# MeshSync.net
KiCad netlist of a schematic drawn in EAGLE
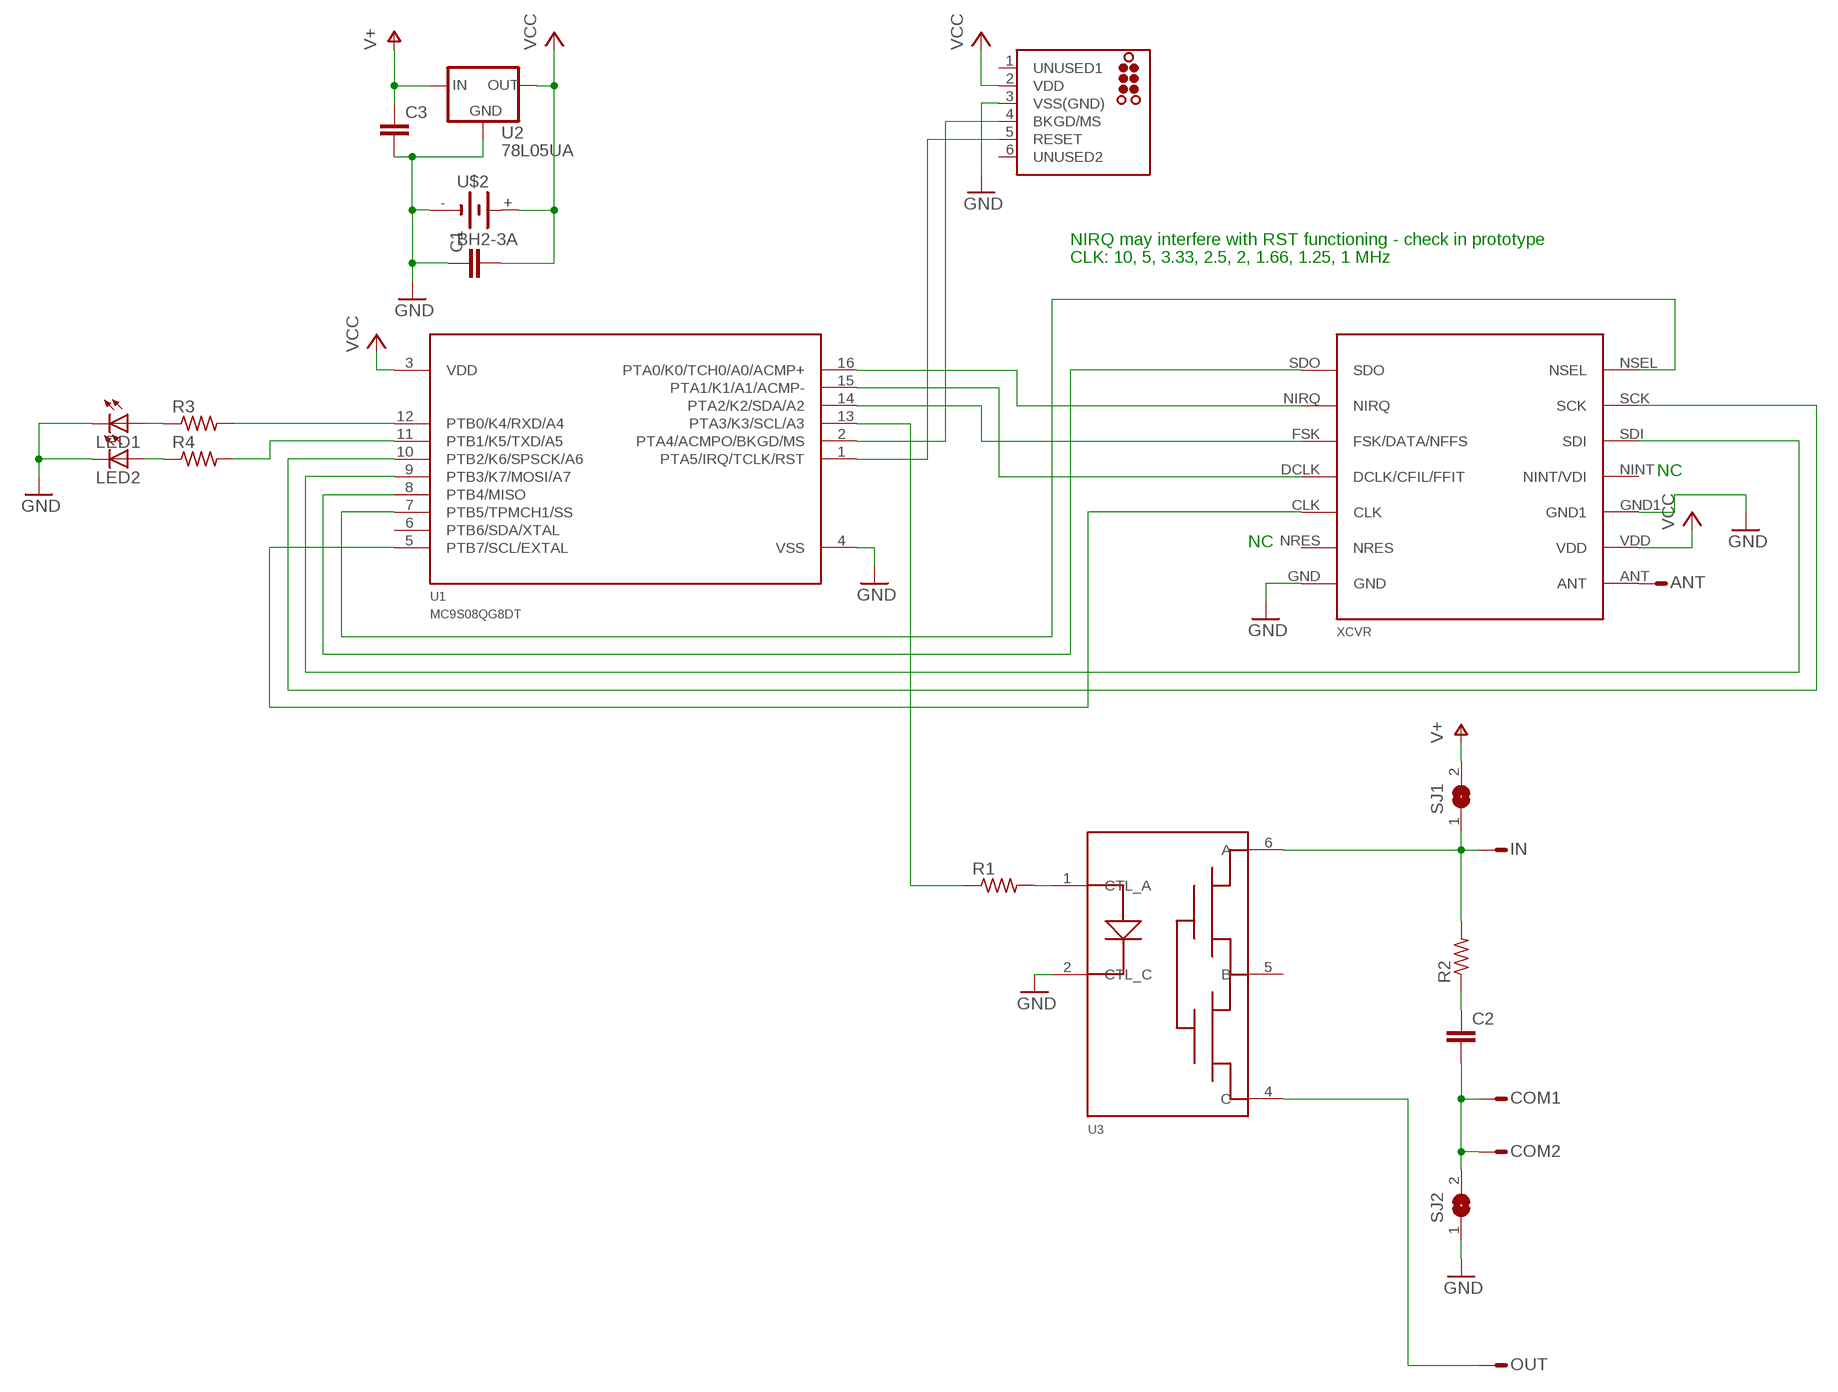
[diagram p0: schematic, sheet 1]

(export (version "E")
  (design (tool "Eeschema 10.0.6"))
  (components
    (comp (ref "ANT")
      (value "PIN")
      (footprint "eagle-import:PINHEAD-1")
      (libsource (lib "eagle-import") (part "PIN"))
    )
    (comp (ref "C1")
      (value "C-EUC0805K")
      (footprint "eagle-import:C0805K")
      (libsource (lib "eagle-import") (part "C-EUC0805K"))
    )
    (comp (ref "C2")
      (value "C-EUC0603K")
      (footprint "eagle-import:C0603K")
      (libsource (lib "eagle-import") (part "C-EUC0603K"))
    )
    (comp (ref "C3")
      (value "C-EUC0603K")
      (footprint "eagle-import:C0603K")
      (libsource (lib "eagle-import") (part "C-EUC0603K"))
    )
    (comp (ref "COM1")
      (value "PIN")
      (footprint "eagle-import:PINHEAD-1")
      (libsource (lib "eagle-import") (part "PIN"))
    )
    (comp (ref "COM2")
      (value "PIN")
      (footprint "eagle-import:PINHEAD-1")
      (libsource (lib "eagle-import") (part "PIN"))
    )
    (comp (ref "IN")
      (value "PIN")
      (footprint "eagle-import:PINHEAD-1")
      (libsource (lib "eagle-import") (part "PIN"))
    )
    (comp (ref "LED1")
      (value "LEDCHIPLED_0603")
      (footprint "eagle-import:CHIPLED_0603")
      (libsource (lib "eagle-import") (part "LEDCHIPLED_0603"))
    )
    (comp (ref "LED2")
      (value "LEDCHIPLED_0603")
      (footprint "eagle-import:CHIPLED_0603")
      (libsource (lib "eagle-import") (part "LEDCHIPLED_0603"))
    )
    (comp (ref "OUT")
      (value "PIN")
      (footprint "eagle-import:PINHEAD-1")
      (libsource (lib "eagle-import") (part "PIN"))
    )
    (comp (ref "R1")
      (value "R0603")
      (footprint "eagle-import:R0603")
      (libsource (lib "eagle-import") (part "R0603"))
    )
    (comp (ref "R2")
      (value "R0603")
      (footprint "eagle-import:R0603")
      (libsource (lib "eagle-import") (part "R0603"))
    )
    (comp (ref "R3")
      (value "R0603")
      (footprint "eagle-import:R0603")
      (libsource (lib "eagle-import") (part "R0603"))
    )
    (comp (ref "R4")
      (value "R0603")
      (footprint "eagle-import:R0603")
      (libsource (lib "eagle-import") (part "R0603"))
    )
    (comp (ref "SJ1")
      (value "SJW")
      (footprint "eagle-import:SJW")
      (libsource (lib "eagle-import") (part "SJW"))
    )
    (comp (ref "SJ2")
      (value "SJW")
      (footprint "eagle-import:SJW")
      (libsource (lib "eagle-import") (part "SJW"))
    )
    (comp (ref "U$1")
      (value "TC2030-MCP-NL")
      (footprint "eagle-import:TC2030-MCP-NL")
      (libsource (lib "eagle-import") (part "TC2030-MCP-NL"))
    )
    (comp (ref "U$2")
      (value "BH2-3A")
      (footprint "eagle-import:BH2-3A")
      (libsource (lib "eagle-import") (part "BH2-3A"))
    )
    (comp (ref "U1")
      (value "MC9S08QG8DT")
      (footprint "eagle-import:TSSOP16")
      (libsource (lib "eagle-import") (part "MC9S08QG8DT"))
    )
    (comp (ref "U2")
      (value "78L05UA")
      (footprint "eagle-import:SOT89")
      (libsource (lib "eagle-import") (part "78L05UA"))
    )
    (comp (ref "U3")
      (value "PVT312")
      (footprint "eagle-import:DIL06-SMT")
      (libsource (lib "eagle-import") (part "PVT312"))
    )
    (comp (ref "XCVR")
      (value "RFM12B")
      (footprint "eagle-import:RFM12B")
      (libsource (lib "eagle-import") (part "RFM12B"))
    )
  )
  (nets
    (net (code "1") (name "GND") (class "Default")
      (node (ref "C1") (pin "1") (pinfunction "1_1") (pintype "passive"))
      (node (ref "C3") (pin "2") (pinfunction "2_2") (pintype "passive"))
      (node (ref "LED1") (pin "C") (pinfunction "C_C") (pintype "passive"))
      (node (ref "LED2") (pin "C") (pinfunction "C_C") (pintype "passive"))
      (node (ref "SJ2") (pin "1") (pinfunction "1_1") (pintype "passive"))
      (node (ref "U$1") (pin "3") (pinfunction "VSS(GND)_3") (pintype "power_in"))
      (node (ref "U$2") (pin "-") (pinfunction "-_-") (pintype "passive"))
      (node (ref "U1") (pin "4") (pinfunction "VSS_4") (pintype "bidirectional"))
      (node (ref "U2") (pin "2") (pinfunction "GND_2") (pintype "input"))
      (node (ref "U3") (pin "2") (pinfunction "CTL_C_2") (pintype "bidirectional"))
      (node (ref "XCVR") (pin "GND") (pinfunction "GND_GND") (pintype "bidirectional"))
      (node (ref "XCVR") (pin "GND1") (pinfunction "GND1_GND1") (pintype "bidirectional"))
    )
    (net (code "2") (name "Net-(ANT-M)") (class "Default")
      (node (ref "ANT") (pin "1") (pinfunction "M_1") (pintype "passive"))
      (node (ref "XCVR") (pin "ANT") (pinfunction "ANT_ANT") (pintype "bidirectional"))
    )
    (net (code "3") (name "Net-(C2-Pad1)") (class "Default")
      (node (ref "C2") (pin "1") (pinfunction "1_1") (pintype "passive"))
      (node (ref "R2") (pin "1") (pinfunction "1_1") (pintype "passive"))
    )
    (net (code "4") (name "Net-(COM1-M)") (class "Default")
      (node (ref "C2") (pin "2") (pinfunction "2_2") (pintype "passive"))
      (node (ref "COM1") (pin "1") (pinfunction "M_1") (pintype "passive"))
      (node (ref "COM2") (pin "1") (pinfunction "M_1") (pintype "passive"))
      (node (ref "SJ2") (pin "2") (pinfunction "2_2") (pintype "passive"))
    )
    (net (code "5") (name "Net-(IN-M)") (class "Default")
      (node (ref "IN") (pin "1") (pinfunction "M_1") (pintype "passive"))
      (node (ref "R2") (pin "2") (pinfunction "2_2") (pintype "passive"))
      (node (ref "SJ1") (pin "1") (pinfunction "1_1") (pintype "passive"))
      (node (ref "U3") (pin "6") (pinfunction "A_6") (pintype "bidirectional"))
    )
    (net (code "6") (name "Net-(LED1-PadA)") (class "Default")
      (node (ref "LED1") (pin "A") (pinfunction "A_A") (pintype "passive"))
      (node (ref "R3") (pin "1") (pinfunction "1_1") (pintype "passive"))
    )
    (net (code "7") (name "Net-(LED2-PadA)") (class "Default")
      (node (ref "LED2") (pin "A") (pinfunction "A_A") (pintype "passive"))
      (node (ref "R4") (pin "1") (pinfunction "1_1") (pintype "passive"))
    )
    (net (code "8") (name "Net-(OUT-M)") (class "Default")
      (node (ref "OUT") (pin "1") (pinfunction "M_1") (pintype "passive"))
      (node (ref "U3") (pin "4") (pinfunction "C_4") (pintype "bidirectional"))
    )
    (net (code "9") (name "Net-(U$1-BKGD{slash}MS)") (class "Default")
      (node (ref "U$1") (pin "4") (pinfunction "BKGD/MS_4") (pintype "bidirectional"))
      (node (ref "U1") (pin "2") (pinfunction "PTA4/ACMPO/BKGD/MS_2") (pintype "bidirectional"))
    )
    (net (code "10") (name "Net-(U$1-RESET)") (class "Default")
      (node (ref "U$1") (pin "5") (pinfunction "RESET_5") (pintype "output"))
      (node (ref "U1") (pin "1") (pinfunction "PTA5/IRQ/TCLK/RST_1") (pintype "bidirectional"))
    )
    (net (code "11") (name "Net-(U1-PTA0{slash}K0{slash}TCH0{slash}A0{slash}ACMP+)") (class "Default")
      (node (ref "U1") (pin "16") (pinfunction "PTA0/K0/TCH0/A0/ACMP+_16") (pintype "bidirectional"))
      (node (ref "XCVR") (pin "NIRQ") (pinfunction "NIRQ_NIRQ") (pintype "bidirectional"))
    )
    (net (code "12") (name "Net-(U1-PTA1{slash}K1{slash}A1{slash}ACMP-)") (class "Default")
      (node (ref "U1") (pin "15") (pinfunction "PTA1/K1/A1/ACMP-_15") (pintype "bidirectional"))
      (node (ref "XCVR") (pin "DCLK") (pinfunction "DCLK/CFIL/FFIT_DCLK") (pintype "bidirectional"))
    )
    (net (code "13") (name "Net-(U1-PTA2{slash}K2{slash}SDA{slash}A2)") (class "Default")
      (node (ref "U1") (pin "14") (pinfunction "PTA2/K2/SDA/A2_14") (pintype "bidirectional"))
      (node (ref "XCVR") (pin "FSK") (pinfunction "FSK/DATA/NFFS_FSK") (pintype "bidirectional"))
    )
    (net (code "14") (name "Net-(U1-PTA3{slash}K3{slash}SCL{slash}A3)") (class "Default")
      (node (ref "R1") (pin "1") (pinfunction "1_1") (pintype "passive"))
      (node (ref "U1") (pin "13") (pinfunction "PTA3/K3/SCL/A3_13") (pintype "bidirectional"))
    )
    (net (code "15") (name "Net-(U1-PTB0{slash}K4{slash}RXD{slash}A4)") (class "Default")
      (node (ref "R3") (pin "2") (pinfunction "2_2") (pintype "passive"))
      (node (ref "U1") (pin "12") (pinfunction "PTB0/K4/RXD/A4_12") (pintype "bidirectional"))
    )
    (net (code "16") (name "Net-(U1-PTB1{slash}K5{slash}TXD{slash}A5)") (class "Default")
      (node (ref "R4") (pin "2") (pinfunction "2_2") (pintype "passive"))
      (node (ref "U1") (pin "11") (pinfunction "PTB1/K5/TXD/A5_11") (pintype "bidirectional"))
    )
    (net (code "17") (name "Net-(U1-PTB2{slash}K6{slash}SPSCK{slash}A6)") (class "Default")
      (node (ref "U1") (pin "10") (pinfunction "PTB2/K6/SPSCK/A6_10") (pintype "bidirectional"))
      (node (ref "XCVR") (pin "SCK") (pinfunction "SCK_SCK") (pintype "bidirectional"))
    )
    (net (code "18") (name "Net-(U1-PTB3{slash}K7{slash}MOSI{slash}A7)") (class "Default")
      (node (ref "U1") (pin "9") (pinfunction "PTB3/K7/MOSI/A7_9") (pintype "bidirectional"))
      (node (ref "XCVR") (pin "SDI") (pinfunction "SDI_SDI") (pintype "bidirectional"))
    )
    (net (code "19") (name "Net-(U1-PTB4{slash}MISO)") (class "Default")
      (node (ref "U1") (pin "8") (pinfunction "PTB4/MISO_8") (pintype "bidirectional"))
      (node (ref "XCVR") (pin "SDO") (pinfunction "SDO_SDO") (pintype "bidirectional"))
    )
    (net (code "20") (name "Net-(U1-PTB5{slash}TPMCH1{slash}SS)") (class "Default")
      (node (ref "U1") (pin "7") (pinfunction "PTB5/TPMCH1/SS_7") (pintype "bidirectional"))
      (node (ref "XCVR") (pin "NSEL") (pinfunction "NSEL_NSEL") (pintype "bidirectional"))
    )
    (net (code "21") (name "Net-(U1-PTB7{slash}SCL{slash}EXTAL)") (class "Default")
      (node (ref "U1") (pin "5") (pinfunction "PTB7/SCL/EXTAL_5") (pintype "bidirectional"))
      (node (ref "XCVR") (pin "CLK") (pinfunction "CLK_CLK") (pintype "bidirectional"))
    )
    (net (code "22") (name "Net-(U3-CTL_A)") (class "Default")
      (node (ref "R1") (pin "2") (pinfunction "2_2") (pintype "passive"))
      (node (ref "U3") (pin "1") (pinfunction "CTL_A_1") (pintype "bidirectional"))
    )
    (net (code "23") (name "V+") (class "Default")
      (node (ref "C3") (pin "1") (pinfunction "1_1") (pintype "passive"))
      (node (ref "SJ1") (pin "2") (pinfunction "2_2") (pintype "passive"))
      (node (ref "U2") (pin "3") (pinfunction "IN_3") (pintype "input"))
    )
    (net (code "24") (name "VCC") (class "Default")
      (node (ref "C1") (pin "2") (pinfunction "2_2") (pintype "passive"))
      (node (ref "U$1") (pin "2") (pinfunction "VDD_2") (pintype "power_in"))
      (node (ref "U$2") (pin "+") (pinfunction "+_+") (pintype "passive"))
      (node (ref "U1") (pin "3") (pinfunction "VDD_3") (pintype "bidirectional"))
      (node (ref "U2") (pin "1") (pinfunction "OUT_1") (pintype "passive"))
      (node (ref "XCVR") (pin "VDD") (pinfunction "VDD_VDD") (pintype "bidirectional"))
    )
    (net (code "25") (name "unconnected-(U$1-UNUSED1-Pad1)") (class "Default")
      (node (ref "U$1") (pin "1") (pinfunction "UNUSED1_1") (pintype "passive"))
    )
    (net (code "26") (name "unconnected-(U$1-UNUSED2-Pad6)") (class "Default")
      (node (ref "U$1") (pin "6") (pinfunction "UNUSED2_6") (pintype "bidirectional"))
    )
    (net (code "27") (name "unconnected-(U1-PTB6{slash}SDA{slash}XTAL-Pad6)") (class "Default")
      (node (ref "U1") (pin "6") (pinfunction "PTB6/SDA/XTAL_6") (pintype "bidirectional"))
    )
    (net (code "28") (name "unconnected-(U3-B-Pad5)") (class "Default")
      (node (ref "U3") (pin "5") (pinfunction "B_5") (pintype "bidirectional"))
    )
    (net (code "29") (name "unconnected-(XCVR-NINT{slash}VDI-PadNINT)") (class "Default")
      (node (ref "XCVR") (pin "NINT") (pinfunction "NINT/VDI_NINT") (pintype "bidirectional"))
    )
    (net (code "30") (name "unconnected-(XCVR-PadNRES)") (class "Default")
      (node (ref "XCVR") (pin "NRES") (pinfunction "NRES_NRES") (pintype "bidirectional"))
    )
  )
)
